# Bypass_FPGA_3V3.net
KiCad netlist of a schematic drawn in Altium Designer
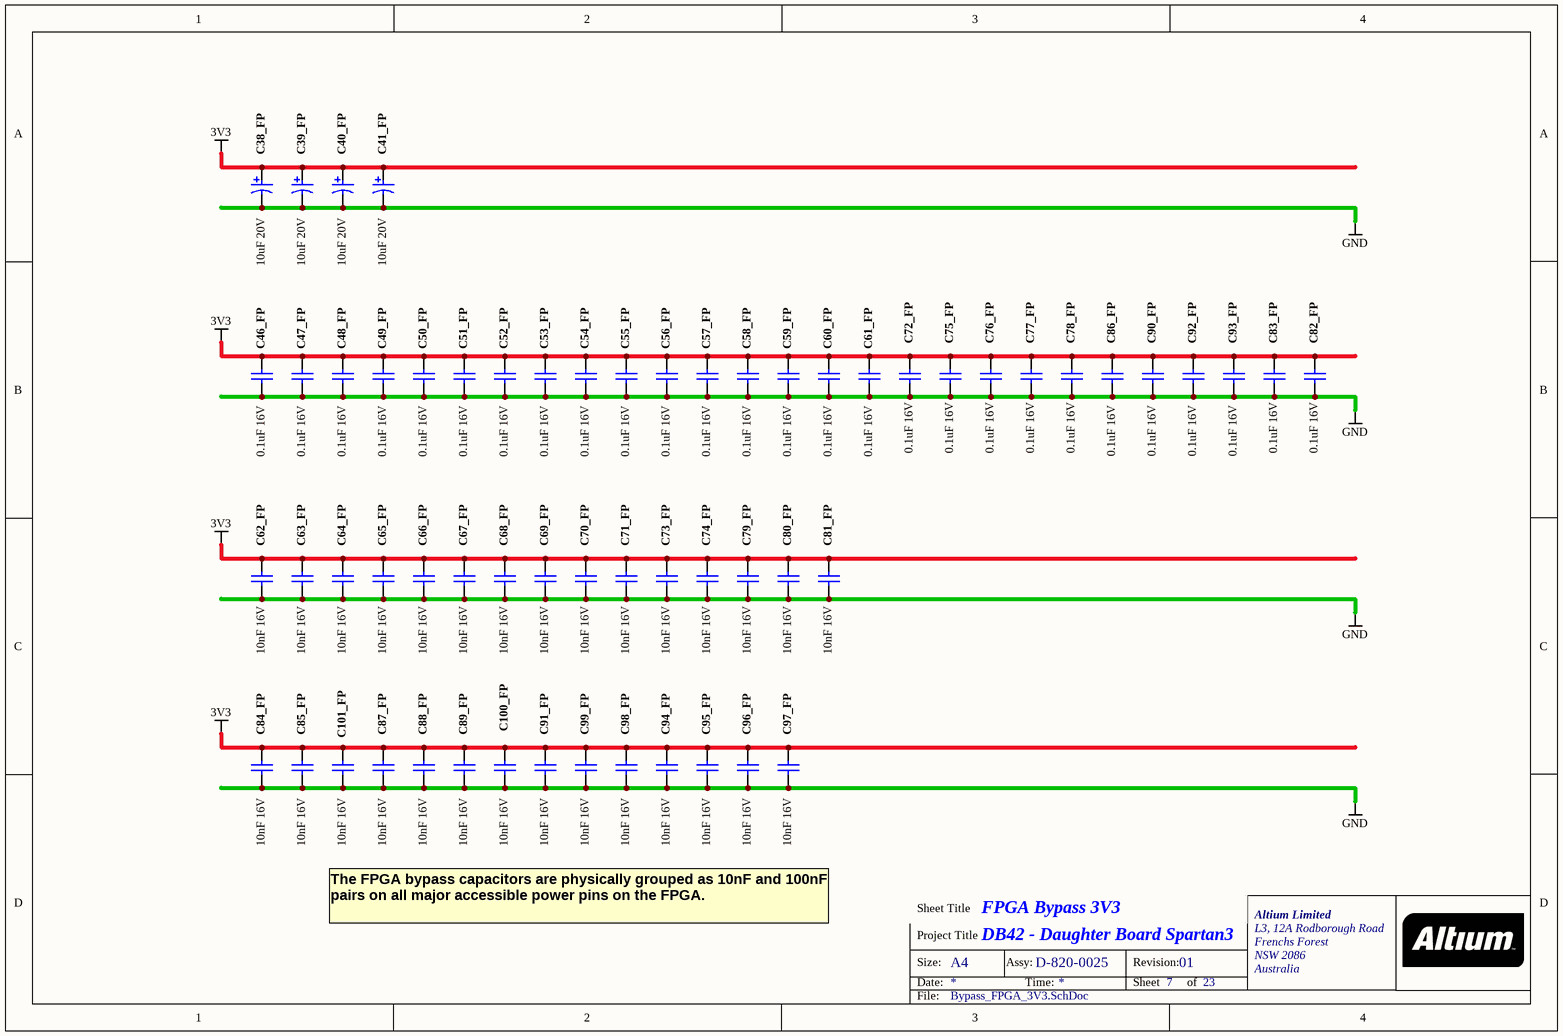
[diagram p0: Bypass_FPGA_3V3.SchDoc]

(export (version "E")
  (design (tool "Eeschema 10.0.6"))
  (components
    (comp (ref "C38_FP")
      (value "10uF 20V")
      (footprint "CAPC3528-STAR")
      (description "Capacitor, Tantalum, 10uF 10% 20V MCCT-B (3528)")
      (fields (field (name "TOLERANCE") "10 %"))
      (libsource (lib "altium-import") (part "root_0_CAP-P_"))
    )
    (comp (ref "C39_FP")
      (value "10uF 20V")
      (footprint "CAPC3528-STAR")
      (description "Capacitor, Tantalum, 10uF 10% 20V MCCT-B (3528)")
      (fields (field (name "TOLERANCE") "10 %"))
      (libsource (lib "altium-import") (part "root_0_CAP-P_"))
    )
    (comp (ref "C40_FP")
      (value "10uF 20V")
      (footprint "CAPC3528-STAR")
      (description "Capacitor, Tantalum, 10uF 10% 20V MCCT-B (3528)")
      (fields (field (name "TOLERANCE") "10 %"))
      (libsource (lib "altium-import") (part "root_0_CAP-P_"))
    )
    (comp (ref "C41_FP")
      (value "10uF 20V")
      (footprint "CAPC3528-STAR")
      (description "Capacitor, Tantalum, 10uF 10% 20V MCCT-B (3528)")
      (fields (field (name "TOLERANCE") "10 %"))
      (libsource (lib "altium-import") (part "root_0_CAP-P_"))
    )
    (comp (ref "C46_FP")
      (value "0.1uF 16V")
      (footprint "CAPC1005-STAR")
      (description "Capacitor, Ceramic, 0.1uF 10% 16V 0402 (1005) X7R")
      (fields (field (name "TOLERANCE") "10 %"))
      (libsource (lib "altium-import") (part "root_0_mirrored_CAP-NP_"))
    )
    (comp (ref "C47_FP")
      (value "0.1uF 16V")
      (footprint "CAPC1005-STAR")
      (description "Capacitor, Ceramic, 0.1uF 10% 16V 0402 (1005) X7R")
      (fields (field (name "TOLERANCE") "10 %"))
      (libsource (lib "altium-import") (part "root_0_mirrored_CAP-NP_"))
    )
    (comp (ref "C48_FP")
      (value "0.1uF 16V")
      (footprint "CAPC1005-STAR")
      (description "Capacitor, Ceramic, 0.1uF 10% 16V 0402 (1005) X7R")
      (fields (field (name "TOLERANCE") "10 %"))
      (libsource (lib "altium-import") (part "root_0_mirrored_CAP-NP_"))
    )
    (comp (ref "C49_FP")
      (value "0.1uF 16V")
      (footprint "CAPC1005-STAR")
      (description "Capacitor, Ceramic, 0.1uF 10% 16V 0402 (1005) X7R")
      (fields (field (name "TOLERANCE") "10 %"))
      (libsource (lib "altium-import") (part "root_0_mirrored_CAP-NP_"))
    )
    (comp (ref "C50_FP")
      (value "0.1uF 16V")
      (footprint "CAPC1005-STAR")
      (description "Capacitor, Ceramic, 0.1uF 10% 16V 0402 (1005) X7R")
      (fields (field (name "TOLERANCE") "10 %"))
      (libsource (lib "altium-import") (part "root_0_mirrored_CAP-NP_"))
    )
    (comp (ref "C51_FP")
      (value "0.1uF 16V")
      (footprint "CAPC1005-STAR")
      (description "Capacitor, Ceramic, 0.1uF 10% 16V 0402 (1005) X7R")
      (fields (field (name "TOLERANCE") "10 %"))
      (libsource (lib "altium-import") (part "root_0_mirrored_CAP-NP_"))
    )
    (comp (ref "C52_FP")
      (value "0.1uF 16V")
      (footprint "CAPC1005-STAR")
      (description "Capacitor, Ceramic, 0.1uF 10% 16V 0402 (1005) X7R")
      (fields (field (name "TOLERANCE") "10 %"))
      (libsource (lib "altium-import") (part "root_0_mirrored_CAP-NP_"))
    )
    (comp (ref "C53_FP")
      (value "0.1uF 16V")
      (footprint "CAPC1005-STAR")
      (description "Capacitor, Ceramic, 0.1uF 10% 16V 0402 (1005) X7R")
      (fields (field (name "TOLERANCE") "10 %"))
      (libsource (lib "altium-import") (part "root_0_mirrored_CAP-NP_"))
    )
    (comp (ref "C54_FP")
      (value "0.1uF 16V")
      (footprint "CAPC1005-STAR")
      (description "Capacitor, Ceramic, 0.1uF 10% 16V 0402 (1005) X7R")
      (fields (field (name "TOLERANCE") "10 %"))
      (libsource (lib "altium-import") (part "root_0_mirrored_CAP-NP_"))
    )
    (comp (ref "C55_FP")
      (value "0.1uF 16V")
      (footprint "CAPC1005-STAR")
      (description "Capacitor, Ceramic, 0.1uF 10% 16V 0402 (1005) X7R")
      (fields (field (name "TOLERANCE") "10 %"))
      (libsource (lib "altium-import") (part "root_0_mirrored_CAP-NP_"))
    )
    (comp (ref "C56_FP")
      (value "0.1uF 16V")
      (footprint "CAPC1005-STAR")
      (description "Capacitor, Ceramic, 0.1uF 10% 16V 0402 (1005) X7R")
      (fields (field (name "TOLERANCE") "10 %"))
      (libsource (lib "altium-import") (part "root_0_mirrored_CAP-NP_"))
    )
    (comp (ref "C57_FP")
      (value "0.1uF 16V")
      (footprint "CAPC1005-STAR")
      (description "Capacitor, Ceramic, 0.1uF 10% 16V 0402 (1005) X7R")
      (fields (field (name "TOLERANCE") "10 %"))
      (libsource (lib "altium-import") (part "root_0_mirrored_CAP-NP_"))
    )
    (comp (ref "C58_FP")
      (value "0.1uF 16V")
      (footprint "CAPC1005-STAR")
      (description "Capacitor, Ceramic, 0.1uF 10% 16V 0402 (1005) X7R")
      (fields (field (name "TOLERANCE") "10 %"))
      (libsource (lib "altium-import") (part "root_0_mirrored_CAP-NP_"))
    )
    (comp (ref "C59_FP")
      (value "0.1uF 16V")
      (footprint "CAPC1005-STAR")
      (description "Capacitor, Ceramic, 0.1uF 10% 16V 0402 (1005) X7R")
      (fields (field (name "TOLERANCE") "10 %"))
      (libsource (lib "altium-import") (part "root_0_mirrored_CAP-NP_"))
    )
    (comp (ref "C60_FP")
      (value "0.1uF 16V")
      (footprint "CAPC1005-STAR")
      (description "Capacitor, Ceramic, 0.1uF 10% 16V 0402 (1005) X7R")
      (fields (field (name "TOLERANCE") "10 %"))
      (libsource (lib "altium-import") (part "root_0_mirrored_CAP-NP_"))
    )
    (comp (ref "C61_FP")
      (value "0.1uF 16V")
      (footprint "CAPC1005-STAR")
      (description "Capacitor, Ceramic, 0.1uF 10% 16V 0402 (1005) X7R")
      (fields (field (name "TOLERANCE") "10 %"))
      (libsource (lib "altium-import") (part "root_0_mirrored_CAP-NP_"))
    )
    (comp (ref "C62_FP")
      (value "10nF 16V")
      (footprint "CAPC1005-STAR")
      (description "Capacitor, Ceramic, 10nF 10% 16V 0402 (1005) X7R")
      (fields (field (name "TOLERANCE") "10 %"))
      (libsource (lib "altium-import") (part "root_0_CAP-NP_"))
    )
    (comp (ref "C63_FP")
      (value "10nF 16V")
      (footprint "CAPC1005-STAR")
      (description "Capacitor, Ceramic, 10nF 10% 16V 0402 (1005) X7R")
      (fields (field (name "TOLERANCE") "10 %"))
      (libsource (lib "altium-import") (part "root_0_CAP-NP_"))
    )
    (comp (ref "C64_FP")
      (value "10nF 16V")
      (footprint "CAPC1005-STAR")
      (description "Capacitor, Ceramic, 10nF 10% 16V 0402 (1005) X7R")
      (fields (field (name "TOLERANCE") "10 %"))
      (libsource (lib "altium-import") (part "root_0_CAP-NP_"))
    )
    (comp (ref "C65_FP")
      (value "10nF 16V")
      (footprint "CAPC1005-STAR")
      (description "Capacitor, Ceramic, 10nF 10% 16V 0402 (1005) X7R")
      (fields (field (name "TOLERANCE") "10 %"))
      (libsource (lib "altium-import") (part "root_0_CAP-NP_"))
    )
    (comp (ref "C66_FP")
      (value "10nF 16V")
      (footprint "CAPC1005-STAR")
      (description "Capacitor, Ceramic, 10nF 10% 16V 0402 (1005) X7R")
      (fields (field (name "TOLERANCE") "10 %"))
      (libsource (lib "altium-import") (part "root_0_CAP-NP_"))
    )
    (comp (ref "C67_FP")
      (value "10nF 16V")
      (footprint "CAPC1005-STAR")
      (description "Capacitor, Ceramic, 10nF 10% 16V 0402 (1005) X7R")
      (fields (field (name "TOLERANCE") "10 %"))
      (libsource (lib "altium-import") (part "root_0_CAP-NP_"))
    )
    (comp (ref "C68_FP")
      (value "10nF 16V")
      (footprint "CAPC1005-STAR")
      (description "Capacitor, Ceramic, 10nF 10% 16V 0402 (1005) X7R")
      (fields (field (name "TOLERANCE") "10 %"))
      (libsource (lib "altium-import") (part "root_0_CAP-NP_"))
    )
    (comp (ref "C69_FP")
      (value "10nF 16V")
      (footprint "CAPC1005-STAR")
      (description "Capacitor, Ceramic, 10nF 10% 16V 0402 (1005) X7R")
      (fields (field (name "TOLERANCE") "10 %"))
      (libsource (lib "altium-import") (part "root_0_CAP-NP_"))
    )
    (comp (ref "C70_FP")
      (value "10nF 16V")
      (footprint "CAPC1005-STAR")
      (description "Capacitor, Ceramic, 10nF 10% 16V 0402 (1005) X7R")
      (fields (field (name "TOLERANCE") "10 %"))
      (libsource (lib "altium-import") (part "root_0_CAP-NP_"))
    )
    (comp (ref "C71_FP")
      (value "10nF 16V")
      (footprint "CAPC1005-STAR")
      (description "Capacitor, Ceramic, 10nF 10% 16V 0402 (1005) X7R")
      (fields (field (name "TOLERANCE") "10 %"))
      (libsource (lib "altium-import") (part "root_0_CAP-NP_"))
    )
    (comp (ref "C72_FP")
      (value "0.1uF 16V")
      (footprint "CAPC1005-STAR")
      (description "Capacitor, Ceramic, 0.1uF 10% 16V 0402 (1005) X7R")
      (fields (field (name "TOLERANCE") "10 %"))
      (libsource (lib "AltiumDesignLibrary") (part "CAP-NP"))
    )
    (comp (ref "C73_FP")
      (value "10nF 16V")
      (footprint "CAPC1005-STAR")
      (description "Capacitor, Ceramic, 10nF 10% 16V 0402 (1005) X7R")
      (fields (field (name "TOLERANCE") "10 %"))
      (libsource (lib "altium-import") (part "root_0_CAP-NP_"))
    )
    (comp (ref "C74_FP")
      (value "10nF 16V")
      (footprint "CAPC1005-STAR")
      (description "Capacitor, Ceramic, 10nF 10% 16V 0402 (1005) X7R")
      (fields (field (name "TOLERANCE") "10 %"))
      (libsource (lib "altium-import") (part "root_0_CAP-NP_"))
    )
    (comp (ref "C75_FP")
      (value "0.1uF 16V")
      (footprint "CAPC1005-STAR")
      (description "Capacitor, Ceramic, 0.1uF 10% 16V 0402 (1005) X7R")
      (fields (field (name "TOLERANCE") "10 %"))
      (libsource (lib "AltiumDesignLibrary") (part "CAP-NP"))
    )
    (comp (ref "C76_FP")
      (value "0.1uF 16V")
      (footprint "CAPC1005-STAR")
      (description "Capacitor, Ceramic, 0.1uF 10% 16V 0402 (1005) X7R")
      (fields (field (name "TOLERANCE") "10 %"))
      (libsource (lib "AltiumDesignLibrary") (part "CAP-NP"))
    )
    (comp (ref "C77_FP")
      (value "0.1uF 16V")
      (footprint "CAPC1005-STAR")
      (description "Capacitor, Ceramic, 0.1uF 10% 16V 0402 (1005) X7R")
      (fields (field (name "TOLERANCE") "10 %"))
      (libsource (lib "AltiumDesignLibrary") (part "CAP-NP"))
    )
    (comp (ref "C78_FP")
      (value "0.1uF 16V")
      (footprint "CAPC1005-STAR")
      (description "Capacitor, Ceramic, 0.1uF 10% 16V 0402 (1005) X7R")
      (fields (field (name "TOLERANCE") "10 %"))
      (libsource (lib "AltiumDesignLibrary") (part "CAP-NP"))
    )
    (comp (ref "C79_FP")
      (value "10nF 16V")
      (footprint "CAPC1005-STAR")
      (description "Capacitor, Ceramic, 10nF 10% 16V 0402 (1005) X7R")
      (fields (field (name "TOLERANCE") "10 %"))
      (libsource (lib "altium-import") (part "root_0_CAP-NP_"))
    )
    (comp (ref "C80_FP")
      (value "10nF 16V")
      (footprint "CAPC1005-STAR")
      (description "Capacitor, Ceramic, 10nF 10% 16V 0402 (1005) X7R")
      (fields (field (name "TOLERANCE") "10 %"))
      (libsource (lib "altium-import") (part "root_0_CAP-NP_"))
    )
    (comp (ref "C81_FP")
      (value "10nF 16V")
      (footprint "CAPC1005-STAR")
      (description "Capacitor, Ceramic, 10nF 10% 16V 0402 (1005) X7R")
      (fields (field (name "TOLERANCE") "10 %"))
      (libsource (lib "altium-import") (part "root_0_CAP-NP_"))
    )
    (comp (ref "C82_FP")
      (value "0.1uF 16V")
      (footprint "CAPC1005-STAR")
      (description "Capacitor, Ceramic, 0.1uF 10% 16V 0402 (1005) X7R")
      (fields (field (name "TOLERANCE") "10 %"))
      (libsource (lib "AltiumDesignLibrary") (part "CAP-NP"))
    )
    (comp (ref "C83_FP")
      (value "0.1uF 16V")
      (footprint "CAPC1005-STAR")
      (description "Capacitor, Ceramic, 0.1uF 10% 16V 0402 (1005) X7R")
      (fields (field (name "TOLERANCE") "10 %"))
      (libsource (lib "AltiumDesignLibrary") (part "CAP-NP"))
    )
    (comp (ref "C84_FP")
      (value "10nF 16V")
      (footprint "CAPC1005-STAR")
      (description "Capacitor, Ceramic, 10nF 10% 16V 0402 (1005) X7R")
      (fields (field (name "TOLERANCE") "10 %"))
      (libsource (lib "altium-import") (part "root_0_CAP-NP_"))
    )
    (comp (ref "C85_FP")
      (value "10nF 16V")
      (footprint "CAPC1005-STAR")
      (description "Capacitor, Ceramic, 10nF 10% 16V 0402 (1005) X7R")
      (fields (field (name "TOLERANCE") "10 %"))
      (libsource (lib "altium-import") (part "root_0_CAP-NP_"))
    )
    (comp (ref "C86_FP")
      (value "0.1uF 16V")
      (footprint "CAPC1005-STAR")
      (description "Capacitor, Ceramic, 0.1uF 10% 16V 0402 (1005) X7R")
      (fields (field (name "TOLERANCE") "10 %"))
      (libsource (lib "AltiumDesignLibrary") (part "CAP-NP"))
    )
    (comp (ref "C87_FP")
      (value "10nF 16V")
      (footprint "CAPC1005-STAR")
      (description "Capacitor, Ceramic, 10nF 10% 16V 0402 (1005) X7R")
      (fields (field (name "TOLERANCE") "10 %"))
      (libsource (lib "altium-import") (part "root_0_CAP-NP_"))
    )
    (comp (ref "C88_FP")
      (value "10nF 16V")
      (footprint "CAPC1005-STAR")
      (description "Capacitor, Ceramic, 10nF 10% 16V 0402 (1005) X7R")
      (fields (field (name "TOLERANCE") "10 %"))
      (libsource (lib "altium-import") (part "root_0_CAP-NP_"))
    )
    (comp (ref "C89_FP")
      (value "10nF 16V")
      (footprint "CAPC1005-STAR")
      (description "Capacitor, Ceramic, 10nF 10% 16V 0402 (1005) X7R")
      (fields (field (name "TOLERANCE") "10 %"))
      (libsource (lib "altium-import") (part "root_0_CAP-NP_"))
    )
    (comp (ref "C90_FP")
      (value "0.1uF 16V")
      (footprint "CAPC1005-STAR")
      (description "Capacitor, Ceramic, 0.1uF 10% 16V 0402 (1005) X7R")
      (fields (field (name "TOLERANCE") "10 %"))
      (libsource (lib "AltiumDesignLibrary") (part "CAP-NP"))
    )
    (comp (ref "C91_FP")
      (value "10nF 16V")
      (footprint "CAPC1005-STAR")
      (description "Capacitor, Ceramic, 10nF 10% 16V 0402 (1005) X7R")
      (fields (field (name "TOLERANCE") "10 %"))
      (libsource (lib "altium-import") (part "root_0_CAP-NP_"))
    )
    (comp (ref "C92_FP")
      (value "0.1uF 16V")
      (footprint "CAPC1005-STAR")
      (description "Capacitor, Ceramic, 0.1uF 10% 16V 0402 (1005) X7R")
      (fields (field (name "TOLERANCE") "10 %"))
      (libsource (lib "AltiumDesignLibrary") (part "CAP-NP"))
    )
    (comp (ref "C93_FP")
      (value "0.1uF 16V")
      (footprint "CAPC1005-STAR")
      (description "Capacitor, Ceramic, 0.1uF 10% 16V 0402 (1005) X7R")
      (fields (field (name "TOLERANCE") "10 %"))
      (libsource (lib "AltiumDesignLibrary") (part "CAP-NP"))
    )
    (comp (ref "C94_FP")
      (value "10nF 16V")
      (footprint "CAPC1005-STAR")
      (description "Capacitor, Ceramic, 10nF 10% 16V 0402 (1005) X7R")
      (fields (field (name "TOLERANCE") "10 %"))
      (libsource (lib "altium-import") (part "root_0_CAP-NP_"))
    )
    (comp (ref "C95_FP")
      (value "10nF 16V")
      (footprint "CAPC1005-STAR")
      (description "Capacitor, Ceramic, 10nF 10% 16V 0402 (1005) X7R")
      (fields (field (name "TOLERANCE") "10 %"))
      (libsource (lib "altium-import") (part "root_0_CAP-NP_"))
    )
    (comp (ref "C96_FP")
      (value "10nF 16V")
      (footprint "CAPC1005-STAR")
      (description "Capacitor, Ceramic, 10nF 10% 16V 0402 (1005) X7R")
      (fields (field (name "TOLERANCE") "10 %"))
      (libsource (lib "altium-import") (part "root_0_CAP-NP_"))
    )
    (comp (ref "C97_FP")
      (value "10nF 16V")
      (footprint "CAPC1005-STAR")
      (description "Capacitor, Ceramic, 10nF 10% 16V 0402 (1005) X7R")
      (fields (field (name "TOLERANCE") "10 %"))
      (libsource (lib "altium-import") (part "root_0_CAP-NP_"))
    )
    (comp (ref "C98_FP")
      (value "10nF 16V")
      (footprint "CAPC1005-STAR")
      (description "Capacitor, Ceramic, 10nF 10% 16V 0402 (1005) X7R")
      (fields (field (name "TOLERANCE") "10 %"))
      (libsource (lib "altium-import") (part "root_0_CAP-NP_"))
    )
    (comp (ref "C99_FP")
      (value "10nF 16V")
      (footprint "CAPC1005-STAR")
      (description "Capacitor, Ceramic, 10nF 10% 16V 0402 (1005) X7R")
      (fields (field (name "TOLERANCE") "10 %"))
      (libsource (lib "altium-import") (part "root_0_CAP-NP_"))
    )
    (comp (ref "C100_FP")
      (value "10nF 16V")
      (footprint "CAPC1005-STAR")
      (description "Capacitor, Ceramic, 10nF 10% 16V 0402 (1005) X7R")
      (fields (field (name "TOLERANCE") "10 %"))
      (libsource (lib "altium-import") (part "root_0_CAP-NP_"))
    )
    (comp (ref "C101_FP")
      (value "10nF 16V")
      (footprint "CAPC1005-STAR")
      (description "Capacitor, Ceramic, 10nF 10% 16V 0402 (1005) X7R")
      (fields (field (name "TOLERANCE") "10 %"))
      (libsource (lib "altium-import") (part "root_0_CAP-NP_"))
    )
  )
  (nets
    (net (code "1") (name "3V3") (class "Default")
      (node (ref "C100_FP") (pin "1") (pinfunction "1_1") (pintype "passive"))
      (node (ref "C101_FP") (pin "1") (pinfunction "1_1") (pintype "passive"))
      (node (ref "C38_FP") (pin "1") (pinfunction "1_1") (pintype "passive"))
      (node (ref "C39_FP") (pin "1") (pinfunction "1_1") (pintype "passive"))
      (node (ref "C40_FP") (pin "1") (pinfunction "1_1") (pintype "passive"))
      (node (ref "C41_FP") (pin "1") (pinfunction "1_1") (pintype "passive"))
      (node (ref "C46_FP") (pin "1") (pinfunction "1_1") (pintype "passive"))
      (node (ref "C47_FP") (pin "1") (pinfunction "1_1") (pintype "passive"))
      (node (ref "C48_FP") (pin "1") (pinfunction "1_1") (pintype "passive"))
      (node (ref "C49_FP") (pin "1") (pinfunction "1_1") (pintype "passive"))
      (node (ref "C50_FP") (pin "1") (pinfunction "1_1") (pintype "passive"))
      (node (ref "C51_FP") (pin "1") (pinfunction "1_1") (pintype "passive"))
      (node (ref "C52_FP") (pin "1") (pinfunction "1_1") (pintype "passive"))
      (node (ref "C53_FP") (pin "1") (pinfunction "1_1") (pintype "passive"))
      (node (ref "C54_FP") (pin "1") (pinfunction "1_1") (pintype "passive"))
      (node (ref "C55_FP") (pin "1") (pinfunction "1_1") (pintype "passive"))
      (node (ref "C56_FP") (pin "1") (pinfunction "1_1") (pintype "passive"))
      (node (ref "C57_FP") (pin "1") (pinfunction "1_1") (pintype "passive"))
      (node (ref "C58_FP") (pin "1") (pinfunction "1_1") (pintype "passive"))
      (node (ref "C59_FP") (pin "1") (pinfunction "1_1") (pintype "passive"))
      (node (ref "C60_FP") (pin "1") (pinfunction "1_1") (pintype "passive"))
      (node (ref "C61_FP") (pin "1") (pinfunction "1_1") (pintype "passive"))
      (node (ref "C62_FP") (pin "1") (pinfunction "1_1") (pintype "passive"))
      (node (ref "C63_FP") (pin "1") (pinfunction "1_1") (pintype "passive"))
      (node (ref "C64_FP") (pin "1") (pinfunction "1_1") (pintype "passive"))
      (node (ref "C65_FP") (pin "1") (pinfunction "1_1") (pintype "passive"))
      (node (ref "C66_FP") (pin "1") (pinfunction "1_1") (pintype "passive"))
      (node (ref "C67_FP") (pin "1") (pinfunction "1_1") (pintype "passive"))
      (node (ref "C68_FP") (pin "1") (pinfunction "1_1") (pintype "passive"))
      (node (ref "C69_FP") (pin "1") (pinfunction "1_1") (pintype "passive"))
      (node (ref "C70_FP") (pin "1") (pinfunction "1_1") (pintype "passive"))
      (node (ref "C71_FP") (pin "1") (pinfunction "1_1") (pintype "passive"))
      (node (ref "C72_FP") (pin "1") (pinfunction "1_1") (pintype "passive"))
      (node (ref "C73_FP") (pin "1") (pinfunction "1_1") (pintype "passive"))
      (node (ref "C74_FP") (pin "1") (pinfunction "1_1") (pintype "passive"))
      (node (ref "C75_FP") (pin "1") (pinfunction "1_1") (pintype "passive"))
      (node (ref "C76_FP") (pin "1") (pinfunction "1_1") (pintype "passive"))
      (node (ref "C77_FP") (pin "1") (pinfunction "1_1") (pintype "passive"))
      (node (ref "C78_FP") (pin "1") (pinfunction "1_1") (pintype "passive"))
      (node (ref "C79_FP") (pin "1") (pinfunction "1_1") (pintype "passive"))
      (node (ref "C80_FP") (pin "1") (pinfunction "1_1") (pintype "passive"))
      (node (ref "C81_FP") (pin "1") (pinfunction "1_1") (pintype "passive"))
      (node (ref "C82_FP") (pin "1") (pinfunction "1_1") (pintype "passive"))
      (node (ref "C83_FP") (pin "1") (pinfunction "1_1") (pintype "passive"))
      (node (ref "C84_FP") (pin "1") (pinfunction "1_1") (pintype "passive"))
      (node (ref "C85_FP") (pin "1") (pinfunction "1_1") (pintype "passive"))
      (node (ref "C86_FP") (pin "1") (pinfunction "1_1") (pintype "passive"))
      (node (ref "C87_FP") (pin "1") (pinfunction "1_1") (pintype "passive"))
      (node (ref "C88_FP") (pin "1") (pinfunction "1_1") (pintype "passive"))
      (node (ref "C89_FP") (pin "1") (pinfunction "1_1") (pintype "passive"))
      (node (ref "C90_FP") (pin "1") (pinfunction "1_1") (pintype "passive"))
      (node (ref "C91_FP") (pin "1") (pinfunction "1_1") (pintype "passive"))
      (node (ref "C92_FP") (pin "1") (pinfunction "1_1") (pintype "passive"))
      (node (ref "C93_FP") (pin "1") (pinfunction "1_1") (pintype "passive"))
      (node (ref "C94_FP") (pin "1") (pinfunction "1_1") (pintype "passive"))
      (node (ref "C95_FP") (pin "1") (pinfunction "1_1") (pintype "passive"))
      (node (ref "C96_FP") (pin "1") (pinfunction "1_1") (pintype "passive"))
      (node (ref "C97_FP") (pin "1") (pinfunction "1_1") (pintype "passive"))
      (node (ref "C98_FP") (pin "1") (pinfunction "1_1") (pintype "passive"))
      (node (ref "C99_FP") (pin "1") (pinfunction "1_1") (pintype "passive"))
    )
    (net (code "2") (name "GND") (class "Default")
      (node (ref "C100_FP") (pin "2") (pinfunction "2_2") (pintype "passive"))
      (node (ref "C101_FP") (pin "2") (pinfunction "2_2") (pintype "passive"))
      (node (ref "C38_FP") (pin "2") (pinfunction "2_2") (pintype "passive"))
      (node (ref "C39_FP") (pin "2") (pinfunction "2_2") (pintype "passive"))
      (node (ref "C40_FP") (pin "2") (pinfunction "2_2") (pintype "passive"))
      (node (ref "C41_FP") (pin "2") (pinfunction "2_2") (pintype "passive"))
      (node (ref "C46_FP") (pin "2") (pinfunction "2_2") (pintype "passive"))
      (node (ref "C47_FP") (pin "2") (pinfunction "2_2") (pintype "passive"))
      (node (ref "C48_FP") (pin "2") (pinfunction "2_2") (pintype "passive"))
      (node (ref "C49_FP") (pin "2") (pinfunction "2_2") (pintype "passive"))
      (node (ref "C50_FP") (pin "2") (pinfunction "2_2") (pintype "passive"))
      (node (ref "C51_FP") (pin "2") (pinfunction "2_2") (pintype "passive"))
      (node (ref "C52_FP") (pin "2") (pinfunction "2_2") (pintype "passive"))
      (node (ref "C53_FP") (pin "2") (pinfunction "2_2") (pintype "passive"))
      (node (ref "C54_FP") (pin "2") (pinfunction "2_2") (pintype "passive"))
      (node (ref "C55_FP") (pin "2") (pinfunction "2_2") (pintype "passive"))
      (node (ref "C56_FP") (pin "2") (pinfunction "2_2") (pintype "passive"))
      (node (ref "C57_FP") (pin "2") (pinfunction "2_2") (pintype "passive"))
      (node (ref "C58_FP") (pin "2") (pinfunction "2_2") (pintype "passive"))
      (node (ref "C59_FP") (pin "2") (pinfunction "2_2") (pintype "passive"))
      (node (ref "C60_FP") (pin "2") (pinfunction "2_2") (pintype "passive"))
      (node (ref "C61_FP") (pin "2") (pinfunction "2_2") (pintype "passive"))
      (node (ref "C62_FP") (pin "2") (pinfunction "2_2") (pintype "passive"))
      (node (ref "C63_FP") (pin "2") (pinfunction "2_2") (pintype "passive"))
      (node (ref "C64_FP") (pin "2") (pinfunction "2_2") (pintype "passive"))
      (node (ref "C65_FP") (pin "2") (pinfunction "2_2") (pintype "passive"))
      (node (ref "C66_FP") (pin "2") (pinfunction "2_2") (pintype "passive"))
      (node (ref "C67_FP") (pin "2") (pinfunction "2_2") (pintype "passive"))
      (node (ref "C68_FP") (pin "2") (pinfunction "2_2") (pintype "passive"))
      (node (ref "C69_FP") (pin "2") (pinfunction "2_2") (pintype "passive"))
      (node (ref "C70_FP") (pin "2") (pinfunction "2_2") (pintype "passive"))
      (node (ref "C71_FP") (pin "2") (pinfunction "2_2") (pintype "passive"))
      (node (ref "C72_FP") (pin "2") (pinfunction "2_2") (pintype "passive"))
      (node (ref "C73_FP") (pin "2") (pinfunction "2_2") (pintype "passive"))
      (node (ref "C74_FP") (pin "2") (pinfunction "2_2") (pintype "passive"))
      (node (ref "C75_FP") (pin "2") (pinfunction "2_2") (pintype "passive"))
      (node (ref "C76_FP") (pin "2") (pinfunction "2_2") (pintype "passive"))
      (node (ref "C77_FP") (pin "2") (pinfunction "2_2") (pintype "passive"))
      (node (ref "C78_FP") (pin "2") (pinfunction "2_2") (pintype "passive"))
      (node (ref "C79_FP") (pin "2") (pinfunction "2_2") (pintype "passive"))
      (node (ref "C80_FP") (pin "2") (pinfunction "2_2") (pintype "passive"))
      (node (ref "C81_FP") (pin "2") (pinfunction "2_2") (pintype "passive"))
      (node (ref "C82_FP") (pin "2") (pinfunction "2_2") (pintype "passive"))
      (node (ref "C83_FP") (pin "2") (pinfunction "2_2") (pintype "passive"))
      (node (ref "C84_FP") (pin "2") (pinfunction "2_2") (pintype "passive"))
      (node (ref "C85_FP") (pin "2") (pinfunction "2_2") (pintype "passive"))
      (node (ref "C86_FP") (pin "2") (pinfunction "2_2") (pintype "passive"))
      (node (ref "C87_FP") (pin "2") (pinfunction "2_2") (pintype "passive"))
      (node (ref "C88_FP") (pin "2") (pinfunction "2_2") (pintype "passive"))
      (node (ref "C89_FP") (pin "2") (pinfunction "2_2") (pintype "passive"))
      (node (ref "C90_FP") (pin "2") (pinfunction "2_2") (pintype "passive"))
      (node (ref "C91_FP") (pin "2") (pinfunction "2_2") (pintype "passive"))
      (node (ref "C92_FP") (pin "2") (pinfunction "2_2") (pintype "passive"))
      (node (ref "C93_FP") (pin "2") (pinfunction "2_2") (pintype "passive"))
      (node (ref "C94_FP") (pin "2") (pinfunction "2_2") (pintype "passive"))
      (node (ref "C95_FP") (pin "2") (pinfunction "2_2") (pintype "passive"))
      (node (ref "C96_FP") (pin "2") (pinfunction "2_2") (pintype "passive"))
      (node (ref "C97_FP") (pin "2") (pinfunction "2_2") (pintype "passive"))
      (node (ref "C98_FP") (pin "2") (pinfunction "2_2") (pintype "passive"))
      (node (ref "C99_FP") (pin "2") (pinfunction "2_2") (pintype "passive"))
    )
  )
)
